# Tiva_C_Base.net
KiCad netlist of a schematic drawn in Altium Designer
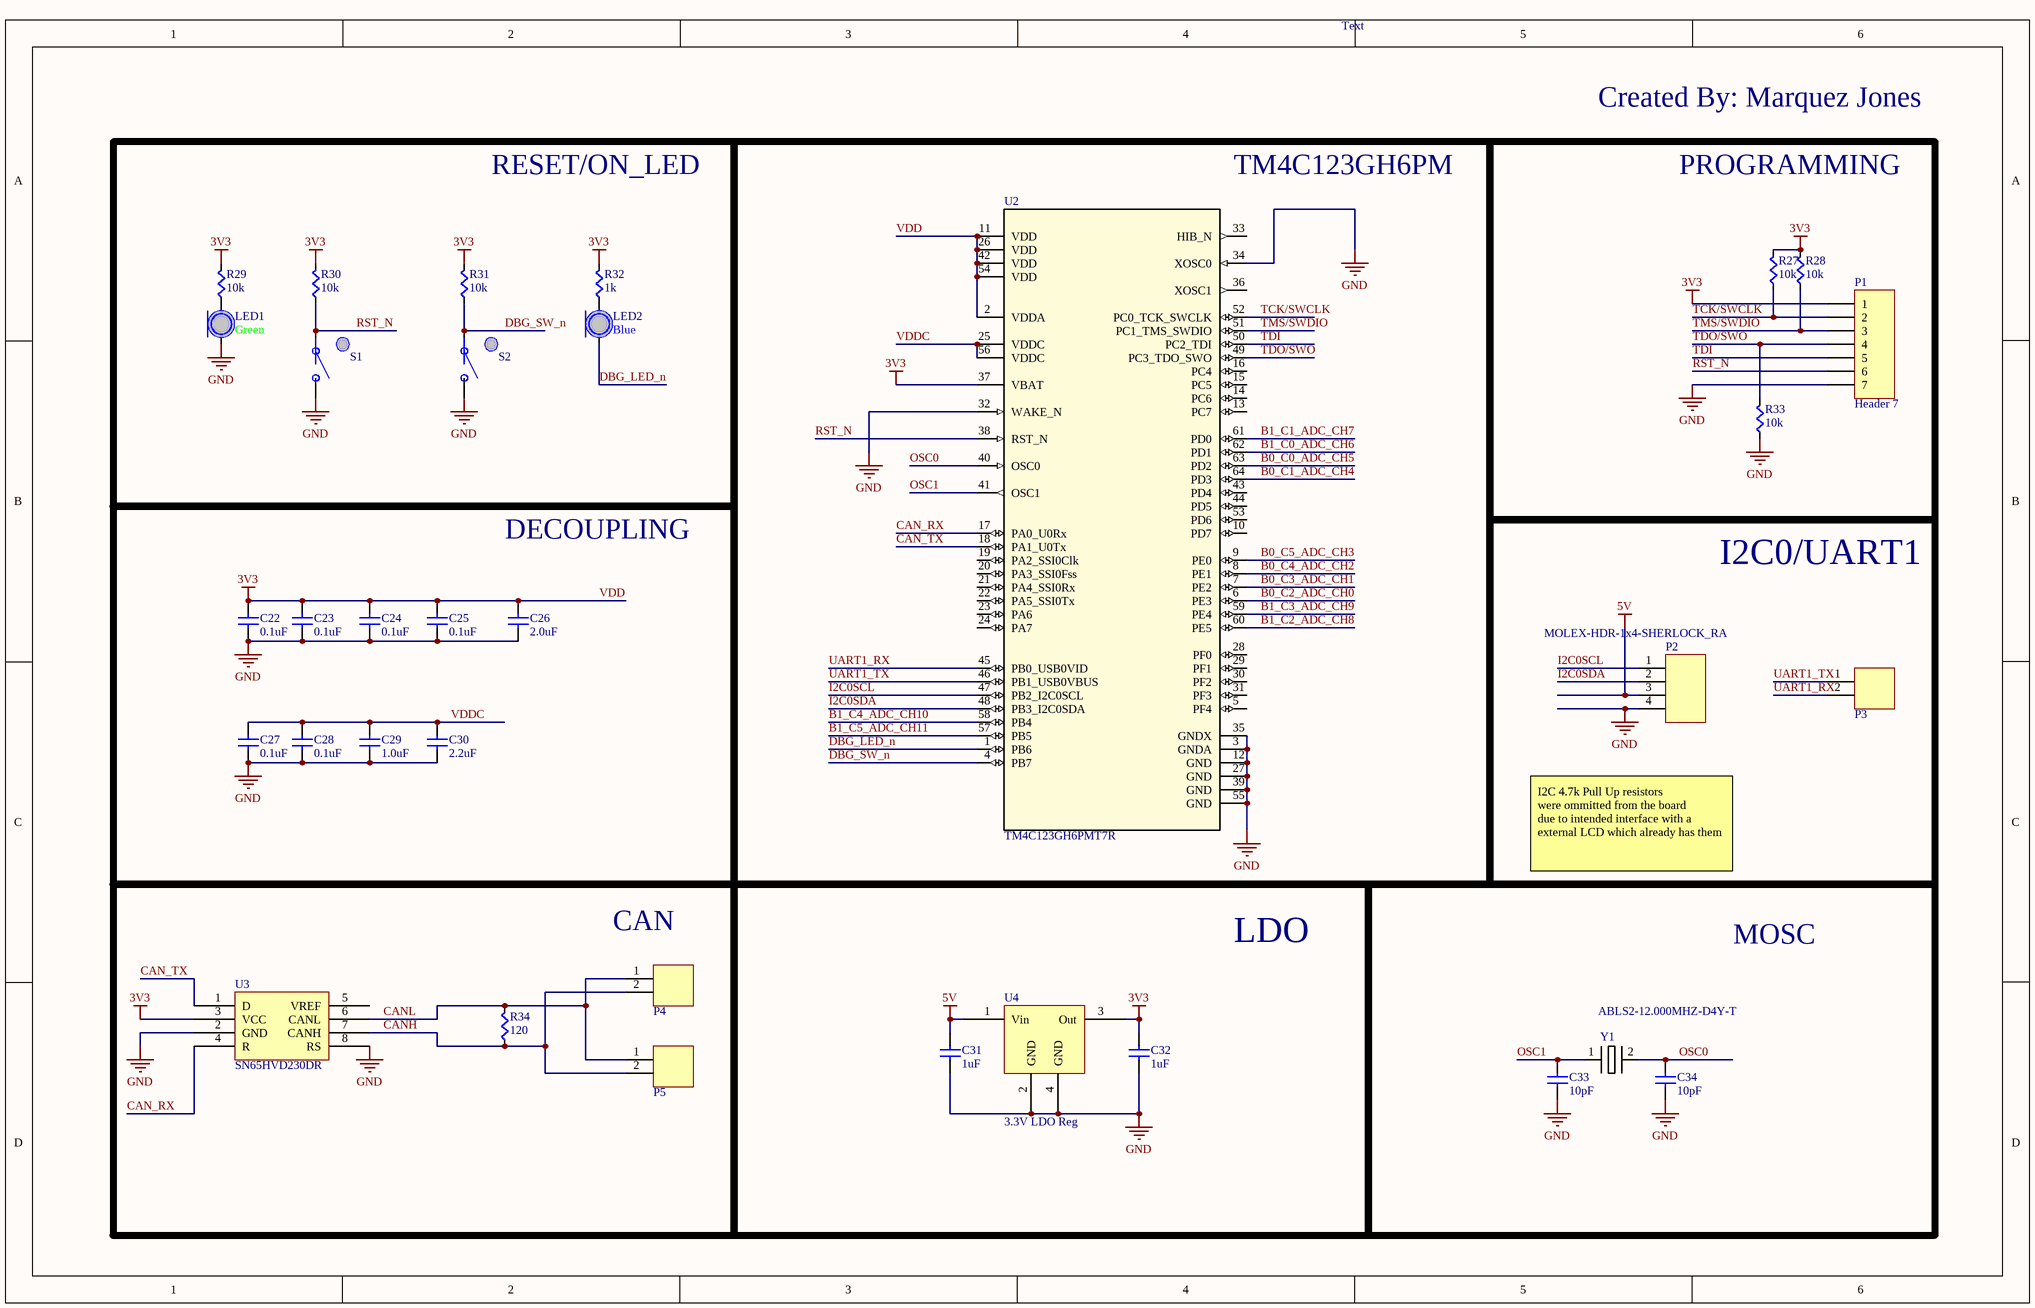
[diagram p0: Tiva_C_Base.SchDoc]

(export (version "E")
  (design (tool "Eeschema 10.0.6"))
  (components
    (comp (ref "C22")
      (value "0.1uF")
      (footprint "CAPC0603")
      (fields (field (name "Comment") "Cap"))
      (libsource (lib "SubjuGator8") (part "Cap"))
    )
    (comp (ref "C23")
      (value "0.1uF")
      (footprint "CAPC0603")
      (fields (field (name "Comment") "Cap"))
      (libsource (lib "SubjuGator8") (part "Cap"))
    )
    (comp (ref "C24")
      (value "0.1uF")
      (footprint "CAPC0603")
      (fields (field (name "Comment") "Cap"))
      (libsource (lib "SubjuGator8") (part "Cap"))
    )
    (comp (ref "C25")
      (value "0.1uF")
      (footprint "CAPC0603")
      (fields (field (name "Comment") "Cap"))
      (libsource (lib "SubjuGator8") (part "Cap"))
    )
    (comp (ref "C26")
      (value "2.0uF")
      (footprint "CAPC0603")
      (fields (field (name "Comment") "Cap"))
      (libsource (lib "SubjuGator8") (part "Cap"))
    )
    (comp (ref "C27")
      (value "0.1uF")
      (footprint "CAPC0603")
      (fields (field (name "Comment") "Cap"))
      (libsource (lib "SubjuGator8") (part "Cap"))
    )
    (comp (ref "C28")
      (value "0.1uF")
      (footprint "CAPC0603")
      (fields (field (name "Comment") "Cap"))
      (libsource (lib "SubjuGator8") (part "Cap"))
    )
    (comp (ref "C29")
      (value "1.0uF")
      (footprint "CAPC0603")
      (fields (field (name "Comment") "Cap"))
      (libsource (lib "SubjuGator8") (part "Cap"))
    )
    (comp (ref "C30")
      (value "2.2uF")
      (footprint "CAPC0603")
      (fields (field (name "Comment") "Cap"))
      (libsource (lib "SubjuGator8") (part "Cap"))
    )
    (comp (ref "C31")
      (value "1uF")
      (footprint "CAPC0603")
      (fields (field (name "MANUFACTURER PART NUMBER") "C0603C105K8PACTU") (field (name "Comment") "Cap"))
      (libsource (lib "SubjuGator8") (part "Cap"))
    )
    (comp (ref "C32")
      (value "1uF")
      (footprint "CAPC0603")
      (fields (field (name "MANUFACTURER PART NUMBER") "C0603C105K8PACTU") (field (name "Comment") "Cap"))
      (libsource (lib "SubjuGator8") (part "Cap"))
    )
    (comp (ref "C33")
      (value "10pF")
      (footprint "CAPC0603")
      (fields (field (name "Comment") "Cap"))
      (libsource (lib "Passives") (part "Cap"))
    )
    (comp (ref "C34")
      (value "10pF")
      (footprint "CAPC0603")
      (fields (field (name "Comment") "Cap"))
      (libsource (lib "Passives") (part "Cap"))
    )
    (comp (ref "LED1")
      (value "LED")
      (footprint "LED0603")
      (fields (field (name "COLOR") "Green"))
      (libsource (lib "SubjuGator8") (part "LED"))
    )
    (comp (ref "LED2")
      (value "LED")
      (footprint "LED0603")
      (fields (field (name "COLOR") "Blue"))
      (libsource (lib "SubjuGator8") (part "LED"))
    )
    (comp (ref "P1")
      (value "Header 7")
      (footprint "HDR1X7")
      (description "Header, 7-Pin")
      (fields (field (name "PUBLISHER") "Altium Limited"))
      (libsource (lib "Miscellaneous Connectors") (part "Header 7"))
    )
    (comp (ref "P2")
      (value "MOLEX-HDR-1x4-SHERLOCK_RA")
      (footprint "MOLEX-HDR-1X4-SHERLOCK-RA")
      (description "Header, Molex, 2mm Pitch Sherlock Header, Single Row, Horizontal, 4 Circuits, Length 3.3mm")
      (fields (field (name "MANUFACTURER PART NUMBER") "0353630460") (field (name "MANUFACTURER") "Molex"))
      (libsource (lib "Connectors") (part "MOLEX-HDR-1x4-SHERLOCK_RA"))
    )
    (comp (ref "P3")
      (value "2-pin Horz Sherlock")
      (footprint "MOLEX-HDR-1X2-SHERLOCK-HORZ")
      (fields
        (field (name "MANUFACTURER PART NUMBER") "0353630260")
        (field (name "MANUFACTURER") "Molex Inc")
      )
      (libsource (lib "Connectors") (part "MOLEX-HDR-1x2-SHERLOCK_RA"))
    )
    (comp (ref "P4")
      (value "2-pin Horz Sherlock")
      (footprint "MOLEX-HDR-1X2-SHERLOCK-HORZ")
      (fields
        (field (name "MANUFACTURER PART NUMBER") "0353630260")
        (field (name "MANUFACTURER") "Molex Inc")
      )
      (libsource (lib "SubjuGator8") (part "MOLEX-HDR-1x2-SHERLOCK_RA"))
    )
    (comp (ref "P5")
      (value "2-pin Horz Sherlock")
      (footprint "MOLEX-HDR-1X2-SHERLOCK-HORZ")
      (fields
        (field (name "MANUFACTURER PART NUMBER") "0353630260")
        (field (name "MANUFACTURER") "Molex Inc")
      )
      (libsource (lib "SubjuGator8") (part "MOLEX-HDR-1x2-SHERLOCK_RA"))
    )
    (comp (ref "R27")
      (value "10k")
      (footprint "RES0603")
      (fields (field (name "Comment") "Res"))
      (libsource (lib "SubjuGator8") (part "Res"))
    )
    (comp (ref "R28")
      (value "10k")
      (footprint "RES0603")
      (fields (field (name "Comment") "Res"))
      (libsource (lib "SubjuGator8") (part "Res"))
    )
    (comp (ref "R29")
      (value "10k")
      (footprint "RES0603")
      (fields (field (name "Comment") "Res"))
      (libsource (lib "SubjuGator8") (part "Res"))
    )
    (comp (ref "R30")
      (value "10k")
      (footprint "RES0603")
      (fields (field (name "Comment") "Res"))
      (libsource (lib "SubjuGator8") (part "Res"))
    )
    (comp (ref "R31")
      (value "10k")
      (footprint "RES0603")
      (fields (field (name "Comment") "Res"))
      (libsource (lib "SubjuGator8") (part "Res"))
    )
    (comp (ref "R32")
      (value "1k")
      (footprint "RES0603")
      (fields (field (name "Comment") "Res"))
      (libsource (lib "SubjuGator8") (part "Res"))
    )
    (comp (ref "R33")
      (value "10k")
      (footprint "RES0603")
      (fields (field (name "Comment") "Res"))
      (libsource (lib "SubjuGator8") (part "Res"))
    )
    (comp (ref "R34")
      (value "120")
      (footprint "RES0603")
      (fields (field (name "Comment") "Res"))
      (libsource (lib "SubjuGator8") (part "Res"))
    )
    (comp (ref "S1")
      (value "Button")
      (footprint "PTS645xxxxSMTR92")
      (description "SPST Button")
      (libsource (lib "SubjuGator8") (part "Button"))
    )
    (comp (ref "S2")
      (value "Button")
      (footprint "PTS645xxxxSMTR92")
      (description "SPST Button")
      (libsource (lib "SubjuGator8") (part "Button"))
    )
    (comp (ref "U2")
      (value "TM4C123GH6PMT7R")
      (footprint "PM0064A_N")
      (description "Imported")
      (fields
        (field (name "PARTNUMBER") "TM4C123GH6PMTR")
        (field (name "ALTERNATE_PARTNUMBER") "TM4C123GH6PMT")
      )
      (libsource (lib "2018-10-31_17-53-54") (part "TM4C123GH6PMT7R"))
    )
    (comp (ref "U3")
      (value "SN65HVD230DR")
      (footprint "SOIC-8pin")
      (description "IC TXRX CAN 1MBPS 3.3V 8SOIC")
      (libsource (lib "SubjuGator8") (part "SN65HVD230DR"))
    )
    (comp (ref "U4")
      (value "3.3V LDO Reg")
      (footprint "SOT23-4n")
      (description "IC REG LDO 3.3V 1A SOT223")
      (libsource (lib "SubjuGator8") (part "LM3940IMPX-3.3"))
    )
    (comp (ref "Y1")
      (value "ABLS2-12.000MHZ-D4Y-T")
      (footprint "HC49/US")
      (description "12MHz ±30ppm Crystal 18pF 50 Ohm -40°C ~ 85°C Surface Mount HC49/US")
      (libsource (lib "ICs") (part "ABLS2-12.000MHZ-D4Y-T"))
    )
  )
  (nets
    (net (code "1") (name "/B0_C0_ADC_CH5") (class "Default")
      (node (ref "U2") (pin "63") (pinfunction "PD2_63") (pintype "bidirectional"))
    )
    (net (code "2") (name "/B0_C1_ADC_CH4") (class "Default")
      (node (ref "U2") (pin "64") (pinfunction "PD3_64") (pintype "bidirectional"))
    )
    (net (code "3") (name "/B0_C2_ADC_CH0") (class "Default")
      (node (ref "U2") (pin "6") (pinfunction "PE3_6") (pintype "bidirectional"))
    )
    (net (code "4") (name "/B0_C3_ADC_CH1") (class "Default")
      (node (ref "U2") (pin "7") (pinfunction "PE2_7") (pintype "bidirectional"))
    )
    (net (code "5") (name "/B0_C4_ADC_CH2") (class "Default")
      (node (ref "U2") (pin "8") (pinfunction "PE1_8") (pintype "bidirectional"))
    )
    (net (code "6") (name "/B0_C5_ADC_CH3") (class "Default")
      (node (ref "U2") (pin "9") (pinfunction "PE0_9") (pintype "bidirectional"))
    )
    (net (code "7") (name "/B1_C0_ADC_CH6") (class "Default")
      (node (ref "U2") (pin "62") (pinfunction "PD1_62") (pintype "bidirectional"))
    )
    (net (code "8") (name "/B1_C1_ADC_CH7") (class "Default")
      (node (ref "U2") (pin "61") (pinfunction "PD0_61") (pintype "bidirectional"))
    )
    (net (code "9") (name "/B1_C2_ADC_CH8") (class "Default")
      (node (ref "U2") (pin "60") (pinfunction "PE5_60") (pintype "bidirectional"))
    )
    (net (code "10") (name "/B1_C3_ADC_CH9") (class "Default")
      (node (ref "U2") (pin "59") (pinfunction "PE4_59") (pintype "bidirectional"))
    )
    (net (code "11") (name "/B1_C4_ADC_CH10") (class "Default")
      (node (ref "U2") (pin "58") (pinfunction "PB4_58") (pintype "bidirectional"))
    )
    (net (code "12") (name "/B1_C5_ADC_CH11") (class "Default")
      (node (ref "U2") (pin "57") (pinfunction "PB5_57") (pintype "bidirectional"))
    )
    (net (code "13") (name "/CANH") (class "Default")
      (node (ref "P4") (pin "2") (pinfunction "2_2") (pintype "passive"))
      (node (ref "P5") (pin "2") (pinfunction "2_2") (pintype "passive"))
      (node (ref "R34") (pin "2") (pinfunction "B_2") (pintype "passive"))
      (node (ref "U3") (pin "7") (pinfunction "CANH_7") (pintype "passive"))
    )
    (net (code "14") (name "/CANL") (class "Default")
      (node (ref "P4") (pin "1") (pinfunction "1_1") (pintype "passive"))
      (node (ref "P5") (pin "1") (pinfunction "1_1") (pintype "passive"))
      (node (ref "R34") (pin "1") (pinfunction "A_1") (pintype "passive"))
      (node (ref "U3") (pin "6") (pinfunction "CANL_6") (pintype "passive"))
    )
    (net (code "15") (name "/CAN_RX") (class "Default")
      (node (ref "U2") (pin "17") (pinfunction "PA0_U0Rx_17") (pintype "bidirectional"))
      (node (ref "U3") (pin "4") (pinfunction "R_4") (pintype "passive"))
    )
    (net (code "16") (name "/CAN_TX") (class "Default")
      (node (ref "U2") (pin "18") (pinfunction "PA1_U0Tx_18") (pintype "bidirectional"))
      (node (ref "U3") (pin "1") (pinfunction "D_1") (pintype "passive"))
    )
    (net (code "17") (name "/DBG_LED_n") (class "Default")
      (node (ref "LED2") (pin "C") (pinfunction "C_C") (pintype "passive"))
      (node (ref "U2") (pin "1") (pinfunction "PB6_1") (pintype "bidirectional"))
    )
    (net (code "18") (name "/DBG_SW_n") (class "Default")
      (node (ref "R31") (pin "2") (pinfunction "B_2") (pintype "passive"))
      (node (ref "S2") (pin "A") (pinfunction "A_A") (pintype "passive"))
      (node (ref "U2") (pin "4") (pinfunction "PB7_4") (pintype "bidirectional"))
    )
    (net (code "19") (name "/I2C0SCL") (class "Default")
      (node (ref "P2") (pin "1") (pinfunction "1_1") (pintype "passive"))
      (node (ref "U2") (pin "47") (pinfunction "PB2_I2C0SCL_47") (pintype "bidirectional"))
    )
    (net (code "20") (name "/I2C0SDA") (class "Default")
      (node (ref "P2") (pin "2") (pinfunction "2_2") (pintype "passive"))
      (node (ref "U2") (pin "48") (pinfunction "PB3_I2C0SDA_48") (pintype "bidirectional"))
    )
    (net (code "21") (name "/OSC0") (class "Default")
      (node (ref "C34") (pin "1") (pinfunction "A_1") (pintype "passive"))
      (node (ref "U2") (pin "40") (pinfunction "OSC0_40") (pintype "input"))
      (node (ref "Y1") (pin "2") (pinfunction "2_2") (pintype "passive"))
    )
    (net (code "22") (name "/OSC1") (class "Default")
      (node (ref "C33") (pin "1") (pinfunction "A_1") (pintype "passive"))
      (node (ref "U2") (pin "41") (pinfunction "OSC1_41") (pintype "output"))
      (node (ref "Y1") (pin "1") (pinfunction "1_1") (pintype "passive"))
    )
    (net (code "23") (name "/RST_N") (class "Default")
      (node (ref "P1") (pin "6") (pinfunction "6_6") (pintype "passive"))
      (node (ref "R30") (pin "2") (pinfunction "B_2") (pintype "passive"))
      (node (ref "S1") (pin "A") (pinfunction "A_A") (pintype "passive"))
      (node (ref "U2") (pin "38") (pinfunction "RST_N_38") (pintype "input"))
    )
    (net (code "24") (name "/TCK{slash}SWCLK") (class "Default")
      (node (ref "P1") (pin "2") (pinfunction "2_2") (pintype "passive"))
      (node (ref "R27") (pin "2") (pinfunction "B_2") (pintype "passive"))
      (node (ref "U2") (pin "52") (pinfunction "PC0_TCK_SWCLK_52") (pintype "bidirectional"))
    )
    (net (code "25") (name "/TDI") (class "Default")
      (node (ref "P1") (pin "5") (pinfunction "5_5") (pintype "passive"))
      (node (ref "U2") (pin "50") (pinfunction "PC2_TDI_50") (pintype "bidirectional"))
    )
    (net (code "26") (name "/TDO{slash}SWO") (class "Default")
      (node (ref "P1") (pin "4") (pinfunction "4_4") (pintype "passive"))
      (node (ref "R33") (pin "1") (pinfunction "A_1") (pintype "passive"))
      (node (ref "U2") (pin "49") (pinfunction "PC3_TDO_SWO_49") (pintype "bidirectional"))
    )
    (net (code "27") (name "/TMS{slash}SWDIO") (class "Default")
      (node (ref "P1") (pin "3") (pinfunction "3_3") (pintype "passive"))
      (node (ref "R28") (pin "2") (pinfunction "B_2") (pintype "passive"))
      (node (ref "U2") (pin "51") (pinfunction "PC1_TMS_SWDIO_51") (pintype "bidirectional"))
    )
    (net (code "28") (name "/UART1_RX") (class "Default")
      (node (ref "P3") (pin "2") (pinfunction "2_2") (pintype "passive"))
      (node (ref "U2") (pin "45") (pinfunction "PB0_USB0VID_45") (pintype "bidirectional"))
    )
    (net (code "29") (name "/UART1_TX") (class "Default")
      (node (ref "P3") (pin "1") (pinfunction "1_1") (pintype "passive"))
      (node (ref "U2") (pin "46") (pinfunction "PB1_USB0VBUS_46") (pintype "bidirectional"))
    )
    (net (code "30") (name "/VDDC") (class "Default")
      (node (ref "C27") (pin "1") (pinfunction "A_1") (pintype "passive"))
      (node (ref "C28") (pin "1") (pinfunction "A_1") (pintype "passive"))
      (node (ref "C29") (pin "1") (pinfunction "A_1") (pintype "passive"))
      (node (ref "C30") (pin "1") (pinfunction "A_1") (pintype "passive"))
      (node (ref "U2") (pin "25") (pinfunction "VDDC_25") (pintype "power_in"))
      (node (ref "U2") (pin "56") (pinfunction "VDDC_56") (pintype "power_in"))
    )
    (net (code "31") (name "3V3") (class "Default")
      (node (ref "C22") (pin "1") (pinfunction "A_1") (pintype "passive"))
      (node (ref "C23") (pin "1") (pinfunction "A_1") (pintype "passive"))
      (node (ref "C24") (pin "1") (pinfunction "A_1") (pintype "passive"))
      (node (ref "C25") (pin "1") (pinfunction "A_1") (pintype "passive"))
      (node (ref "C26") (pin "1") (pinfunction "A_1") (pintype "passive"))
      (node (ref "C32") (pin "1") (pinfunction "A_1") (pintype "passive"))
      (node (ref "P1") (pin "1") (pinfunction "1_1") (pintype "passive"))
      (node (ref "R27") (pin "1") (pinfunction "A_1") (pintype "passive"))
      (node (ref "R28") (pin "1") (pinfunction "A_1") (pintype "passive"))
      (node (ref "R29") (pin "1") (pinfunction "A_1") (pintype "passive"))
      (node (ref "R30") (pin "1") (pinfunction "A_1") (pintype "passive"))
      (node (ref "R31") (pin "1") (pinfunction "A_1") (pintype "passive"))
      (node (ref "R32") (pin "1") (pinfunction "A_1") (pintype "passive"))
      (node (ref "U2") (pin "11") (pinfunction "VDD_11") (pintype "power_in"))
      (node (ref "U2") (pin "2") (pinfunction "VDDA_2") (pintype "power_in"))
      (node (ref "U2") (pin "26") (pinfunction "VDD_26") (pintype "power_in"))
      (node (ref "U2") (pin "37") (pinfunction "VBAT_37") (pintype "power_in"))
      (node (ref "U2") (pin "42") (pinfunction "VDD_42") (pintype "power_in"))
      (node (ref "U2") (pin "54") (pinfunction "VDD_54") (pintype "power_in"))
      (node (ref "U3") (pin "3") (pinfunction "VCC_3") (pintype "passive"))
      (node (ref "U4") (pin "3") (pinfunction "Out_3") (pintype "passive"))
    )
    (net (code "32") (name "5V") (class "Default")
      (node (ref "C31") (pin "1") (pinfunction "A_1") (pintype "passive"))
      (node (ref "P2") (pin "3") (pinfunction "3_3") (pintype "passive"))
      (node (ref "U4") (pin "1") (pinfunction "Vin_1") (pintype "passive"))
    )
    (net (code "33") (name "GND") (class "Default")
      (node (ref "C22") (pin "2") (pinfunction "B_2") (pintype "passive"))
      (node (ref "C23") (pin "2") (pinfunction "B_2") (pintype "passive"))
      (node (ref "C24") (pin "2") (pinfunction "B_2") (pintype "passive"))
      (node (ref "C25") (pin "2") (pinfunction "B_2") (pintype "passive"))
      (node (ref "C26") (pin "2") (pinfunction "B_2") (pintype "passive"))
      (node (ref "C27") (pin "2") (pinfunction "B_2") (pintype "passive"))
      (node (ref "C28") (pin "2") (pinfunction "B_2") (pintype "passive"))
      (node (ref "C29") (pin "2") (pinfunction "B_2") (pintype "passive"))
      (node (ref "C30") (pin "2") (pinfunction "B_2") (pintype "passive"))
      (node (ref "C31") (pin "2") (pinfunction "B_2") (pintype "passive"))
      (node (ref "C32") (pin "2") (pinfunction "B_2") (pintype "passive"))
      (node (ref "C33") (pin "2") (pinfunction "B_2") (pintype "passive"))
      (node (ref "C34") (pin "2") (pinfunction "B_2") (pintype "passive"))
      (node (ref "LED1") (pin "C") (pinfunction "C_C") (pintype "passive"))
      (node (ref "P1") (pin "7") (pinfunction "7_7") (pintype "passive"))
      (node (ref "P2") (pin "4") (pinfunction "4_4") (pintype "passive"))
      (node (ref "R33") (pin "2") (pinfunction "B_2") (pintype "passive"))
      (node (ref "S1") (pin "B") (pinfunction "B_B") (pintype "passive"))
      (node (ref "S2") (pin "B") (pinfunction "B_B") (pintype "passive"))
      (node (ref "U2") (pin "12") (pinfunction "GND_12") (pintype "power_in"))
      (node (ref "U2") (pin "27") (pinfunction "GND_27") (pintype "power_in"))
      (node (ref "U2") (pin "3") (pinfunction "GNDA_3") (pintype "power_in"))
      (node (ref "U2") (pin "32") (pinfunction "WAKE_N_32") (pintype "input"))
      (node (ref "U2") (pin "34") (pinfunction "XOSC0_34") (pintype "input"))
      (node (ref "U2") (pin "35") (pinfunction "GNDX_35") (pintype "power_in"))
      (node (ref "U2") (pin "39") (pinfunction "GND_39") (pintype "power_in"))
      (node (ref "U2") (pin "55") (pinfunction "GND_55") (pintype "power_in"))
      (node (ref "U3") (pin "2") (pinfunction "GND_2") (pintype "passive"))
      (node (ref "U3") (pin "8") (pinfunction "RS_8") (pintype "passive"))
      (node (ref "U4") (pin "2") (pinfunction "GND_2") (pintype "passive"))
      (node (ref "U4") (pin "4") (pinfunction "GND_4") (pintype "passive"))
    )
    (net (code "34") (name "Net-(R29-B)") (class "Default")
      (node (ref "LED1") (pin "A") (pinfunction "A_A") (pintype "passive"))
      (node (ref "R29") (pin "2") (pinfunction "B_2") (pintype "passive"))
    )
    (net (code "35") (name "Net-(R32-B)") (class "Default")
      (node (ref "LED2") (pin "A") (pinfunction "A_A") (pintype "passive"))
      (node (ref "R32") (pin "2") (pinfunction "B_2") (pintype "passive"))
    )
    (net (code "36") (name "unconnected-(U2-HIB_N-Pad33)") (class "Default")
      (node (ref "U2") (pin "33") (pinfunction "HIB_N_33") (pintype "output"))
    )
    (net (code "37") (name "unconnected-(U2-PA2_SSI0Clk-Pad19)") (class "Default")
      (node (ref "U2") (pin "19") (pinfunction "PA2_SSI0Clk_19") (pintype "bidirectional"))
    )
    (net (code "38") (name "unconnected-(U2-PA3_SSI0Fss-Pad20)") (class "Default")
      (node (ref "U2") (pin "20") (pinfunction "PA3_SSI0Fss_20") (pintype "bidirectional"))
    )
    (net (code "39") (name "unconnected-(U2-PA4_SSI0Rx-Pad21)") (class "Default")
      (node (ref "U2") (pin "21") (pinfunction "PA4_SSI0Rx_21") (pintype "bidirectional"))
    )
    (net (code "40") (name "unconnected-(U2-PA5_SSI0Tx-Pad22)") (class "Default")
      (node (ref "U2") (pin "22") (pinfunction "PA5_SSI0Tx_22") (pintype "bidirectional"))
    )
    (net (code "41") (name "unconnected-(U2-PA6-Pad23)") (class "Default")
      (node (ref "U2") (pin "23") (pinfunction "PA6_23") (pintype "bidirectional"))
    )
    (net (code "42") (name "unconnected-(U2-PA7-Pad24)") (class "Default")
      (node (ref "U2") (pin "24") (pinfunction "PA7_24") (pintype "bidirectional"))
    )
    (net (code "43") (name "unconnected-(U2-PC4-Pad16)") (class "Default")
      (node (ref "U2") (pin "16") (pinfunction "PC4_16") (pintype "bidirectional"))
    )
    (net (code "44") (name "unconnected-(U2-PC5-Pad15)") (class "Default")
      (node (ref "U2") (pin "15") (pinfunction "PC5_15") (pintype "bidirectional"))
    )
    (net (code "45") (name "unconnected-(U2-PC6-Pad14)") (class "Default")
      (node (ref "U2") (pin "14") (pinfunction "PC6_14") (pintype "bidirectional"))
    )
    (net (code "46") (name "unconnected-(U2-PC7-Pad13)") (class "Default")
      (node (ref "U2") (pin "13") (pinfunction "PC7_13") (pintype "bidirectional"))
    )
    (net (code "47") (name "unconnected-(U2-PD4-Pad43)") (class "Default")
      (node (ref "U2") (pin "43") (pinfunction "PD4_43") (pintype "bidirectional"))
    )
    (net (code "48") (name "unconnected-(U2-PD5-Pad44)") (class "Default")
      (node (ref "U2") (pin "44") (pinfunction "PD5_44") (pintype "bidirectional"))
    )
    (net (code "49") (name "unconnected-(U2-PD6-Pad53)") (class "Default")
      (node (ref "U2") (pin "53") (pinfunction "PD6_53") (pintype "bidirectional"))
    )
    (net (code "50") (name "unconnected-(U2-PD7-Pad10)") (class "Default")
      (node (ref "U2") (pin "10") (pinfunction "PD7_10") (pintype "bidirectional"))
    )
    (net (code "51") (name "unconnected-(U2-PF0-Pad28)") (class "Default")
      (node (ref "U2") (pin "28") (pinfunction "PF0_28") (pintype "bidirectional"))
    )
    (net (code "52") (name "unconnected-(U2-PF1-Pad29)") (class "Default")
      (node (ref "U2") (pin "29") (pinfunction "PF1_29") (pintype "bidirectional"))
    )
    (net (code "53") (name "unconnected-(U2-PF2-Pad30)") (class "Default")
      (node (ref "U2") (pin "30") (pinfunction "PF2_30") (pintype "bidirectional"))
    )
    (net (code "54") (name "unconnected-(U2-PF3-Pad31)") (class "Default")
      (node (ref "U2") (pin "31") (pinfunction "PF3_31") (pintype "bidirectional"))
    )
    (net (code "55") (name "unconnected-(U2-PF4-Pad5)") (class "Default")
      (node (ref "U2") (pin "5") (pinfunction "PF4_5") (pintype "bidirectional"))
    )
    (net (code "56") (name "unconnected-(U2-XOSC1-Pad36)") (class "Default")
      (node (ref "U2") (pin "36") (pinfunction "XOSC1_36") (pintype "output"))
    )
    (net (code "57") (name "unconnected-(U3-VREF-Pad5)") (class "Default")
      (node (ref "U3") (pin "5") (pinfunction "VREF_5") (pintype "passive"))
    )
  )
)
